# MIDI_Shield.net
KiCad netlist of a schematic drawn in EAGLE
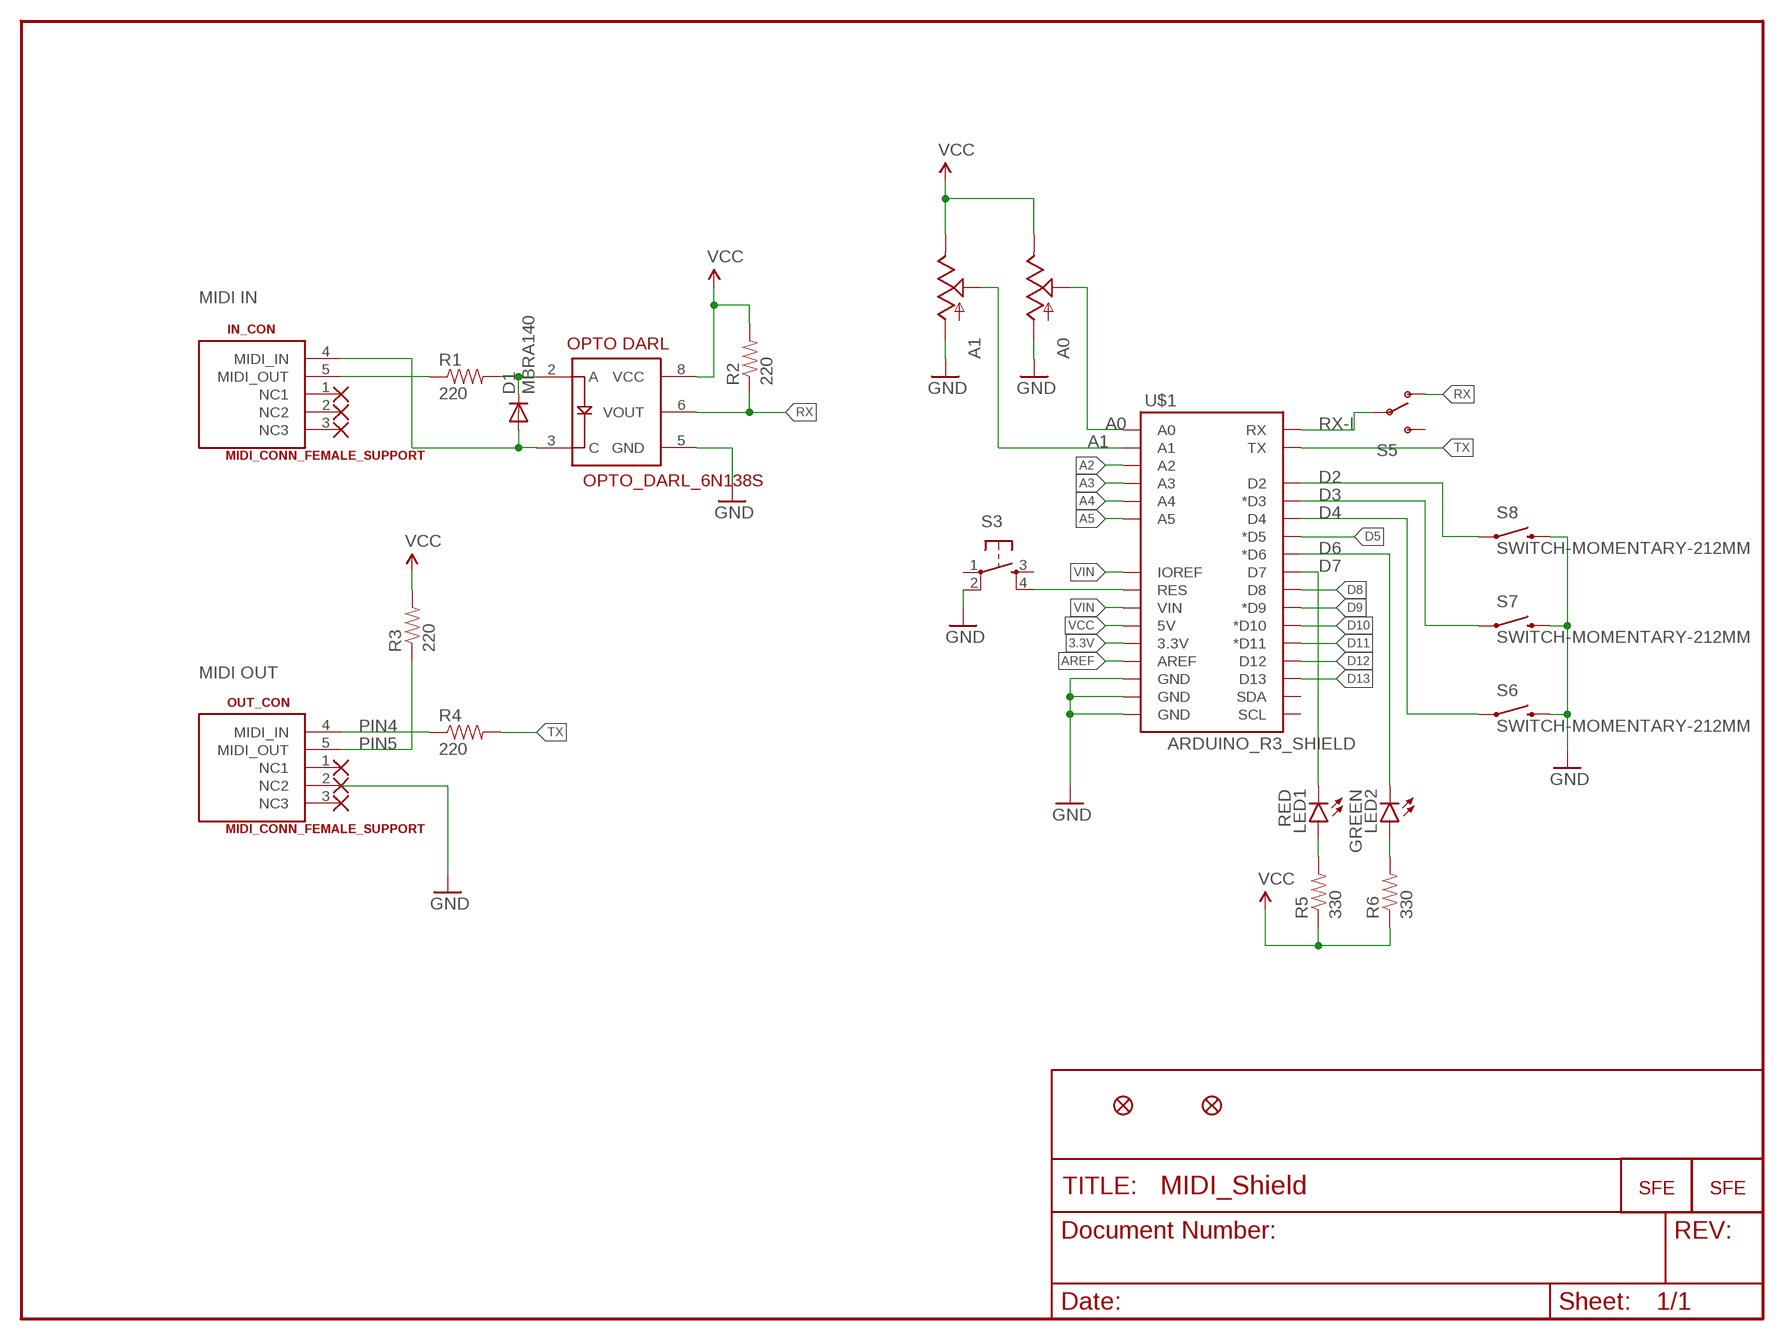
[diagram p0: schematic, sheet 1]

(export (version "E")
  (design (tool "Eeschema 10.0.6"))
  (components
    (comp (ref "A0")
      (value "POT")
      (footprint "eagle-import:ALPS_POT")
      (libsource (lib "eagle-import") (part "POT"))
    )
    (comp (ref "A1")
      (value "POT")
      (footprint "eagle-import:ALPS_POT")
      (libsource (lib "eagle-import") (part "POT"))
    )
    (comp (ref "D1")
      (value "MBRA140")
      (footprint "eagle-import:SMA-DIODE")
      (libsource (lib "eagle-import") (part "DIODESMA"))
    )
    (comp (ref "IN_CON")
      (value "MIDI_CONN_FEMALE_SUPPORT")
      (footprint "eagle-import:DIN_5_FEMALE_SUPPORT")
      (libsource (lib "eagle-import") (part "MIDI_CONN_FEMALE_SUPPORT"))
    )
    (comp (ref "JP1")
      (value "FIDUCIALUFIDUCIAL")
      (footprint "eagle-import:MICRO-FIDUCIAL")
      (libsource (lib "eagle-import") (part "FIDUCIALUFIDUCIAL"))
    )
    (comp (ref "JP2")
      (value "FIDUCIALUFIDUCIAL")
      (footprint "eagle-import:MICRO-FIDUCIAL")
      (libsource (lib "eagle-import") (part "FIDUCIALUFIDUCIAL"))
    )
    (comp (ref "JP3")
      (value "LOGO-SFENEW")
      (footprint "eagle-import:SFE-NEW-WEBLOGO")
      (libsource (lib "eagle-import") (part "LOGO-SFENEW"))
    )
    (comp (ref "JP4")
      (value "LOGO-SFESK")
      (footprint "eagle-import:SFE-LOGO-FLAME")
      (libsource (lib "eagle-import") (part "LOGO-SFESK"))
    )
    (comp (ref "LED1")
      (value "RED")
      (footprint "eagle-import:LED-0603")
      (libsource (lib "eagle-import") (part "LED-RED0603"))
    )
    (comp (ref "LED2")
      (value "GREEN")
      (footprint "eagle-import:LED-0603")
      (libsource (lib "eagle-import") (part "LED-GREEN0603"))
    )
    (comp (ref "OUT_CON")
      (value "MIDI_CONN_FEMALE_SUPPORT")
      (footprint "eagle-import:DIN_5_FEMALE_SUPPORT")
      (libsource (lib "eagle-import") (part "MIDI_CONN_FEMALE_SUPPORT"))
    )
    (comp (ref "R1")
      (value "220")
      (footprint "eagle-import:0603-RES")
      (libsource (lib "eagle-import") (part "220KOHM1/10W1%(0603)"))
    )
    (comp (ref "R2")
      (value "220")
      (footprint "eagle-import:0603-RES")
      (libsource (lib "eagle-import") (part "220KOHM1/10W1%(0603)"))
    )
    (comp (ref "R3")
      (value "220")
      (footprint "eagle-import:0603-RES")
      (libsource (lib "eagle-import") (part "220KOHM1/10W1%(0603)"))
    )
    (comp (ref "R4")
      (value "220")
      (footprint "eagle-import:0603-RES")
      (libsource (lib "eagle-import") (part "220KOHM1/10W1%(0603)"))
    )
    (comp (ref "R5")
      (value "330")
      (footprint "eagle-import:0603-RES")
      (libsource (lib "eagle-import") (part "330OHM1/10W1%(0603)"))
    )
    (comp (ref "R6")
      (value "330")
      (footprint "eagle-import:0603-RES")
      (libsource (lib "eagle-import") (part "330OHM1/10W1%(0603)"))
    )
    (comp (ref "S3")
      (value "TAC_SWITCHSMD")
      (footprint "eagle-import:TACTILE_SWITCH_SMD")
      (libsource (lib "eagle-import") (part "TAC_SWITCHSMD"))
    )
    (comp (ref "S5")
      (value "SWITCH-SPSTSMD")
      (footprint "eagle-import:AYZ0202")
      (libsource (lib "eagle-import") (part "SWITCH-SPSTSMD"))
    )
    (comp (ref "S6")
      (value "SWITCH-MOMENTARY-212MM")
      (footprint "eagle-import:TACTILE-PTH-12MM")
      (libsource (lib "eagle-import") (part "SWITCH-MOMENTARY-212MM"))
    )
    (comp (ref "S7")
      (value "SWITCH-MOMENTARY-212MM")
      (footprint "eagle-import:TACTILE-PTH-12MM")
      (libsource (lib "eagle-import") (part "SWITCH-MOMENTARY-212MM"))
    )
    (comp (ref "S8")
      (value "SWITCH-MOMENTARY-212MM")
      (footprint "eagle-import:TACTILE-PTH-12MM")
      (libsource (lib "eagle-import") (part "SWITCH-MOMENTARY-212MM"))
    )
    (comp (ref "U$1")
      (value "ARDUINO_R3_SHIELD")
      (footprint "eagle-import:UNO_R3_SHIELD")
      (libsource (lib "eagle-import") (part "ARDUINO_R3_SHIELD"))
    )
    (comp (ref "U$6")
      (value "OPTO_DARL_6N138S")
      (footprint "eagle-import:8-SMD")
      (libsource (lib "eagle-import") (part "OPTO_DARL_6N138S"))
    )
  )
  (nets
    (net (code "1") (name "/A0") (class "Default")
      (node (ref "A0") (pin "P$2") (pinfunction "S_P$2") (pintype "passive"))
      (node (ref "U$1") (pin "A0") (pinfunction "A0_A0") (pintype "bidirectional"))
    )
    (net (code "2") (name "/A1") (class "Default")
      (node (ref "A1") (pin "P$2") (pinfunction "S_P$2") (pintype "passive"))
      (node (ref "U$1") (pin "A1") (pinfunction "A1_A1") (pintype "bidirectional"))
    )
    (net (code "3") (name "/D2") (class "Default")
      (node (ref "S8") (pin "1") (pinfunction "1_1") (pintype "passive"))
      (node (ref "U$1") (pin "D2") (pinfunction "D2_D2") (pintype "bidirectional"))
    )
    (net (code "4") (name "/D3") (class "Default")
      (node (ref "S7") (pin "1") (pinfunction "1_1") (pintype "passive"))
      (node (ref "U$1") (pin "D3") (pinfunction "*D3_D3") (pintype "bidirectional"))
    )
    (net (code "5") (name "/D4") (class "Default")
      (node (ref "S6") (pin "1") (pinfunction "1_1") (pintype "passive"))
      (node (ref "U$1") (pin "D4") (pinfunction "D4_D4") (pintype "bidirectional"))
    )
    (net (code "6") (name "/D6") (class "Default")
      (node (ref "LED2") (pin "C") (pinfunction "C_C") (pintype "passive"))
      (node (ref "U$1") (pin "D6") (pinfunction "*D6_D6") (pintype "bidirectional"))
    )
    (net (code "7") (name "/D7") (class "Default")
      (node (ref "LED1") (pin "C") (pinfunction "C_C") (pintype "passive"))
      (node (ref "U$1") (pin "D7") (pinfunction "D7_D7") (pintype "bidirectional"))
    )
    (net (code "8") (name "/RX-I") (class "Default")
      (node (ref "S5") (pin "2") (pinfunction "P_2") (pintype "passive"))
      (node (ref "U$1") (pin "RX") (pinfunction "RX_RX") (pintype "bidirectional"))
    )
    (net (code "9") (name "3.3V") (class "Default")
      (node (ref "U$1") (pin "3.3V") (pinfunction "3.3V_3.3V") (pintype "bidirectional"))
    )
    (net (code "10") (name "A2") (class "Default")
      (node (ref "U$1") (pin "A2") (pinfunction "A2_A2") (pintype "bidirectional"))
    )
    (net (code "11") (name "A3") (class "Default")
      (node (ref "U$1") (pin "A3") (pinfunction "A3_A3") (pintype "bidirectional"))
    )
    (net (code "12") (name "A4") (class "Default")
      (node (ref "U$1") (pin "A4") (pinfunction "A4_A4") (pintype "bidirectional"))
    )
    (net (code "13") (name "A5") (class "Default")
      (node (ref "U$1") (pin "A5") (pinfunction "A5_A5") (pintype "bidirectional"))
    )
    (net (code "14") (name "AREF") (class "Default")
      (node (ref "U$1") (pin "AREF") (pinfunction "AREF_AREF") (pintype "bidirectional"))
    )
    (net (code "15") (name "D5") (class "Default")
      (node (ref "U$1") (pin "D5") (pinfunction "*D5_D5") (pintype "bidirectional"))
    )
    (net (code "16") (name "D8") (class "Default")
      (node (ref "U$1") (pin "D8") (pinfunction "D8_D8") (pintype "bidirectional"))
    )
    (net (code "17") (name "D9") (class "Default")
      (node (ref "U$1") (pin "D9") (pinfunction "*D9_D9") (pintype "bidirectional"))
    )
    (net (code "18") (name "D10") (class "Default")
      (node (ref "U$1") (pin "D10") (pinfunction "*D10_D10") (pintype "bidirectional"))
    )
    (net (code "19") (name "D11") (class "Default")
      (node (ref "U$1") (pin "D11") (pinfunction "*D11_D11") (pintype "bidirectional"))
    )
    (net (code "20") (name "D12") (class "Default")
      (node (ref "U$1") (pin "D12") (pinfunction "D12_D12") (pintype "bidirectional"))
    )
    (net (code "21") (name "D13") (class "Default")
      (node (ref "U$1") (pin "D13") (pinfunction "D13_D13") (pintype "bidirectional"))
    )
    (net (code "22") (name "GND") (class "Default")
      (node (ref "A0") (pin "P$3") (pinfunction "A_P$3") (pintype "passive"))
      (node (ref "A1") (pin "P$3") (pinfunction "A_P$3") (pintype "passive"))
      (node (ref "OUT_CON") (pin "2") (pinfunction "NC2_2") (pintype "bidirectional"))
      (node (ref "S3") (pin "2") (pinfunction "2_2") (pintype "passive"))
      (node (ref "S6") (pin "3") (pinfunction "2_3") (pintype "passive"))
      (node (ref "S7") (pin "3") (pinfunction "2_3") (pintype "passive"))
      (node (ref "S8") (pin "3") (pinfunction "2_3") (pintype "passive"))
      (node (ref "U$1") (pin "GND@0") (pinfunction "GND_GND@0") (pintype "bidirectional"))
      (node (ref "U$1") (pin "GND@1") (pinfunction "GND_GND@1") (pintype "bidirectional"))
      (node (ref "U$1") (pin "GND@2") (pinfunction "GND_GND@2") (pintype "bidirectional"))
      (node (ref "U$6") (pin "5") (pinfunction "GND_5") (pintype "bidirectional"))
    )
    (net (code "23") (name "Net-(IN_CON-MIDI_IN)") (class "Default")
      (node (ref "D1") (pin "A") (pinfunction "A_A") (pintype "passive"))
      (node (ref "IN_CON") (pin "4") (pinfunction "MIDI_IN_4") (pintype "bidirectional"))
      (node (ref "U$6") (pin "3") (pinfunction "C_3") (pintype "bidirectional"))
    )
    (net (code "24") (name "Net-(IN_CON-MIDI_OUT)") (class "Default")
      (node (ref "IN_CON") (pin "5") (pinfunction "MIDI_OUT_5") (pintype "bidirectional"))
      (node (ref "R1") (pin "1") (pinfunction "1_1") (pintype "passive"))
    )
    (net (code "25") (name "Net-(LED1-PadA)") (class "Default")
      (node (ref "LED1") (pin "A") (pinfunction "A_A") (pintype "passive"))
      (node (ref "R5") (pin "2") (pinfunction "2_2") (pintype "passive"))
    )
    (net (code "26") (name "Net-(LED2-PadA)") (class "Default")
      (node (ref "LED2") (pin "A") (pinfunction "A_A") (pintype "passive"))
      (node (ref "R6") (pin "2") (pinfunction "2_2") (pintype "passive"))
    )
    (net (code "27") (name "Net-(OUT_CON-MIDI_IN)") (class "Default")
      (node (ref "OUT_CON") (pin "4") (pinfunction "MIDI_IN_4") (pintype "bidirectional"))
      (node (ref "R4") (pin "1") (pinfunction "1_1") (pintype "passive"))
    )
    (net (code "28") (name "Net-(OUT_CON-MIDI_OUT)") (class "Default")
      (node (ref "OUT_CON") (pin "5") (pinfunction "MIDI_OUT_5") (pintype "bidirectional"))
      (node (ref "R3") (pin "1") (pinfunction "1_1") (pintype "passive"))
    )
    (net (code "29") (name "Net-(U$6-A)") (class "Default")
      (node (ref "D1") (pin "C") (pinfunction "C_C") (pintype "passive"))
      (node (ref "R1") (pin "2") (pinfunction "2_2") (pintype "passive"))
      (node (ref "U$6") (pin "2") (pinfunction "A_2") (pintype "bidirectional"))
    )
    (net (code "30") (name "RX") (class "Default")
      (node (ref "R2") (pin "1") (pinfunction "1_1") (pintype "passive"))
      (node (ref "S5") (pin "1") (pinfunction "O_1") (pintype "passive"))
      (node (ref "U$6") (pin "6") (pinfunction "VOUT_6") (pintype "bidirectional"))
    )
    (net (code "31") (name "TX") (class "Default")
      (node (ref "R4") (pin "2") (pinfunction "2_2") (pintype "passive"))
      (node (ref "U$1") (pin "TX") (pinfunction "TX_TX") (pintype "bidirectional"))
    )
    (net (code "32") (name "VCC") (class "Default")
      (node (ref "A0") (pin "P$1") (pinfunction "E_P$1") (pintype "passive"))
      (node (ref "A1") (pin "P$1") (pinfunction "E_P$1") (pintype "passive"))
      (node (ref "R2") (pin "2") (pinfunction "2_2") (pintype "passive"))
      (node (ref "R3") (pin "2") (pinfunction "2_2") (pintype "passive"))
      (node (ref "R5") (pin "1") (pinfunction "1_1") (pintype "passive"))
      (node (ref "R6") (pin "1") (pinfunction "1_1") (pintype "passive"))
      (node (ref "S3") (pin "4") (pinfunction "4_4") (pintype "passive"))
      (node (ref "U$1") (pin "5V") (pinfunction "5V_5V") (pintype "bidirectional"))
      (node (ref "U$1") (pin "RES") (pinfunction "RES_RES") (pintype "bidirectional"))
      (node (ref "U$6") (pin "8") (pinfunction "VCC_8") (pintype "bidirectional"))
    )
    (net (code "33") (name "VIN") (class "Default")
      (node (ref "U$1") (pin "IOREF") (pinfunction "IOREF_IOREF") (pintype "bidirectional"))
      (node (ref "U$1") (pin "VIN") (pinfunction "VIN_VIN") (pintype "bidirectional"))
    )
    (net (code "34") (name "unconnected-(IN_CON-NC1-Pad1)") (class "Default")
      (node (ref "IN_CON") (pin "1") (pinfunction "NC1_1") (pintype "bidirectional"))
    )
    (net (code "35") (name "unconnected-(IN_CON-NC2-Pad2)") (class "Default")
      (node (ref "IN_CON") (pin "2") (pinfunction "NC2_2") (pintype "bidirectional"))
    )
    (net (code "36") (name "unconnected-(IN_CON-NC3-Pad3)") (class "Default")
      (node (ref "IN_CON") (pin "3") (pinfunction "NC3_3") (pintype "bidirectional"))
    )
    (net (code "37") (name "unconnected-(OUT_CON-NC1-Pad1)") (class "Default")
      (node (ref "OUT_CON") (pin "1") (pinfunction "NC1_1") (pintype "bidirectional"))
    )
    (net (code "38") (name "unconnected-(OUT_CON-NC3-Pad3)") (class "Default")
      (node (ref "OUT_CON") (pin "3") (pinfunction "NC3_3") (pintype "bidirectional"))
    )
    (net (code "39") (name "unconnected-(S3-Pad1)") (class "Default")
      (node (ref "S3") (pin "1") (pinfunction "1_1") (pintype "passive"))
    )
    (net (code "40") (name "unconnected-(S3-Pad3)") (class "Default")
      (node (ref "S3") (pin "3") (pinfunction "3_3") (pintype "passive"))
    )
    (net (code "41") (name "unconnected-(S5-S-Pad3)") (class "Default")
      (node (ref "S5") (pin "3") (pinfunction "S_3") (pintype "passive"))
    )
    (net (code "42") (name "unconnected-(U$1-PadSCL)") (class "Default")
      (node (ref "U$1") (pin "SCL") (pinfunction "SCL_SCL") (pintype "bidirectional"))
    )
    (net (code "43") (name "unconnected-(U$1-PadSDA)") (class "Default")
      (node (ref "U$1") (pin "SDA") (pinfunction "SDA_SDA") (pintype "bidirectional"))
    )
  )
)
